# ChargeLevel.net
KiCad netlist of a schematic drawn in Altium Designer
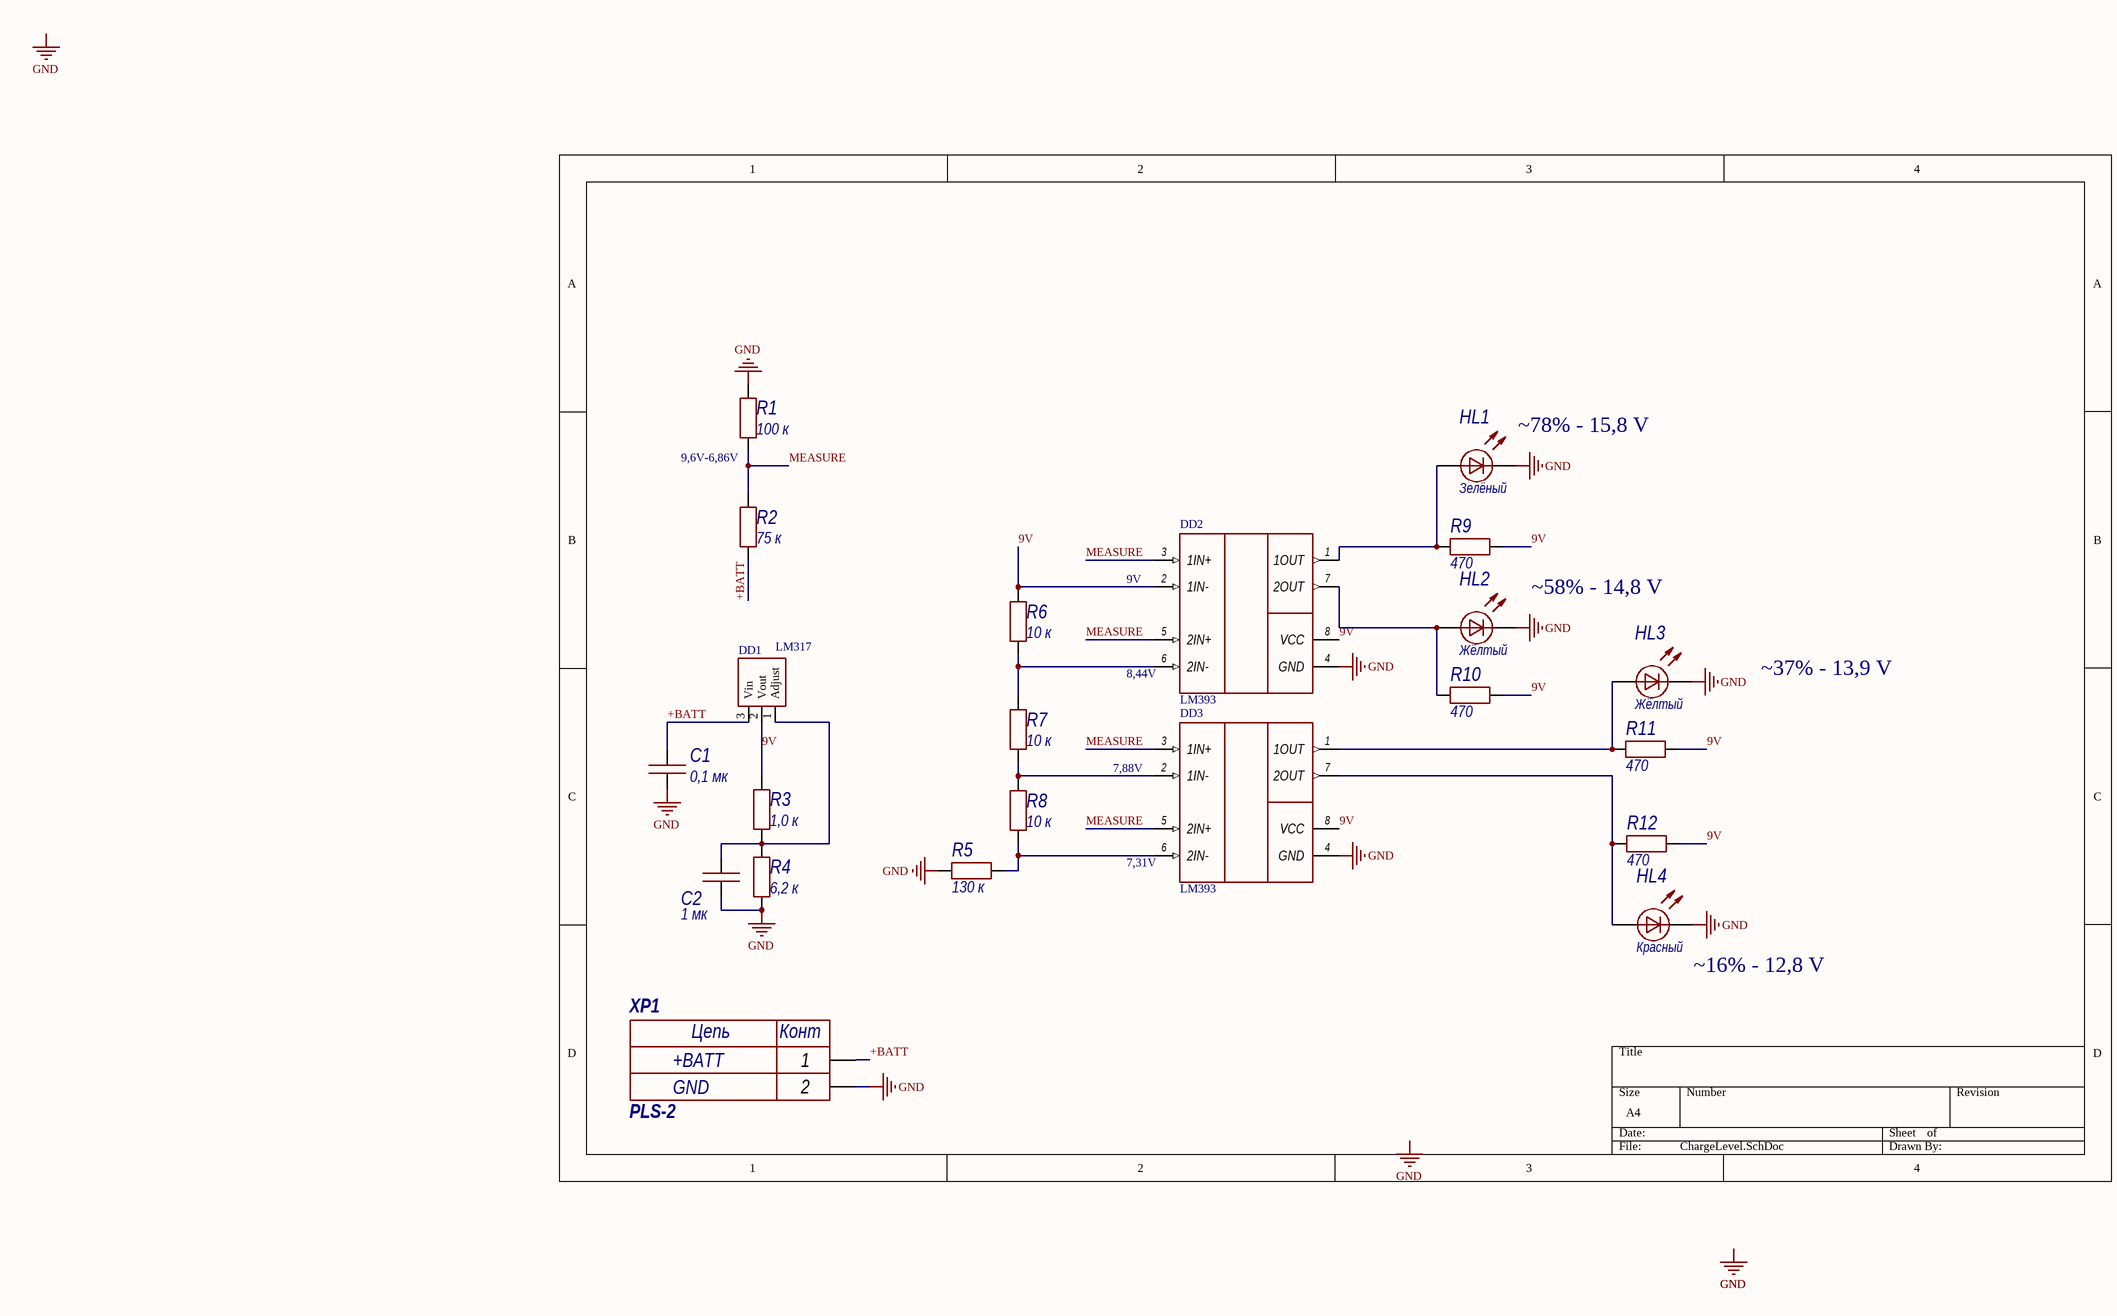
[diagram p0: ChargeLevel.SchDoc]

(export (version "E")
  (design (tool "Eeschema 10.0.6"))
  (components
    (comp (ref "C1")
      (value "0,1 мк")
      (footprint "0603C")
      (description "Конденсатор")
      (fields (field (name "PART NUMBER") "Capacitor"))
      (libsource (lib "Hydrolib") (part "Capacitor"))
    )
    (comp (ref "C2")
      (value "1 мк")
      (footprint "0603C")
      (description "Конденсатор")
      (fields (field (name "PART NUMBER") "Capacitor"))
      (libsource (lib "Hydrolib") (part "Capacitor"))
    )
    (comp (ref "DD1") (value "LM317") (footprint "TO-220") (libsource (lib "LM317") (part "LM317")))
    (comp (ref "DD2")
      (value "LM393")
      (footprint "SOIC-8")
      (description "Двойной маломощный компаратор напряжения")
      (fields
        (field (name "MF") "Texas Instruments")
        (field (name "MP") "LM393D")
        (field (name "АВТОР") "rreali")
      )
      (libsource (lib "Hydrolib") (part "LM393"))
    )
    (comp (ref "DD3")
      (value "LM393")
      (footprint "SOIC-8")
      (description "Двойной маломощный компаратор напряжения")
      (fields
        (field (name "MF") "Texas Instruments")
        (field (name "MP") "LM393D")
        (field (name "АВТОР") "rreali")
      )
      (libsource (lib "Hydrolib") (part "LM393"))
    )
    (comp (ref "HL1")
      (value "Зелёный")
      (footprint "0603D_green")
      (description "Светодиод 0603 Зелёный")
      (fields (field (name "PART NUMBER") "LED 0603 GREEN") (field (name "АВТОР") "rreali"))
      (libsource (lib "Hydrolib") (part "LED"))
    )
    (comp (ref "HL2")
      (value "Жёлтый")
      (footprint "0603D_yellow")
      (description "Светодиод 0603 Жёлтый")
      (fields (field (name "PART NUMBER") "LED 0603 YELLOW") (field (name "АВТОР") "rreali"))
      (libsource (lib "Hydrolib") (part "LED"))
    )
    (comp (ref "HL3")
      (value "Жёлтый")
      (footprint "0603D_yellow")
      (description "Светодиод 0603 Жёлтый")
      (fields (field (name "PART NUMBER") "LED 0603 YELLOW") (field (name "АВТОР") "rreali"))
      (libsource (lib "Hydrolib") (part "LED"))
    )
    (comp (ref "HL4")
      (value "Красный")
      (footprint "0603D_red")
      (description "Светодиод 0603 Красный")
      (fields (field (name "PART NUMBER") "LED 0603 RED") (field (name "АВТОР") "rreali"))
      (libsource (lib "Hydrolib") (part "LED"))
    )
    (comp (ref "R1")
      (value "100 к")
      (footprint "0603R")
      (description "Резистор номиналом 100 кОм 1%")
      (fields (field (name "PART NUMBER") "Resistor_100k_1_0603") (field (name "TOLERANCE") "1%"))
      (libsource (lib "Hydrolib") (part "Resistor"))
    )
    (comp (ref "R2")
      (value "75 к")
      (footprint "0603R")
      (description "Резистор номиналом 75 кОм 1%")
      (fields (field (name "PART NUMBER") "Resistor_75k_1_0603") (field (name "TOLERANCE") "1%"))
      (libsource (lib "Hydrolib") (part "Resistor"))
    )
    (comp (ref "R3")
      (value "1,0 к")
      (footprint "0603R")
      (description "Резистор номиналом 1,0 кОм 1%")
      (fields (field (name "PART NUMBER") "Resistor_1.0k_1_0603") (field (name "TOLERANCE") "1%"))
      (libsource (lib "Hydrolib") (part "Resistor"))
    )
    (comp (ref "R4")
      (value "6,2 к")
      (footprint "0603R")
      (description "Резистор номиналом 6,2 кОм 1%")
      (fields (field (name "PART NUMBER") "Resistor_6.2k_1_0603") (field (name "TOLERANCE") "1%"))
      (libsource (lib "Hydrolib") (part "Resistor"))
    )
    (comp (ref "R5")
      (value "130 к")
      (footprint "0603R")
      (description "Резистор номиналом 130 кОм 1%")
      (fields (field (name "PART NUMBER") "Resistor_130k_1_0603") (field (name "TOLERANCE") "1%"))
      (libsource (lib "") (part "Resistor_1"))
    )
    (comp (ref "R6")
      (value "10 к")
      (footprint "0603R")
      (description "Резистор номиналом 10 кОм 1%")
      (fields (field (name "PART NUMBER") "Resistor_10k_1_0603") (field (name "TOLERANCE") "1%"))
      (libsource (lib "Hydrolib") (part "Resistor"))
    )
    (comp (ref "R7")
      (value "10 к")
      (footprint "0603R")
      (description "Резистор номиналом 10 кОм 1%")
      (fields (field (name "PART NUMBER") "Resistor_10k_1_0603") (field (name "TOLERANCE") "1%"))
      (libsource (lib "Hydrolib") (part "Resistor"))
    )
    (comp (ref "R8")
      (value "10 к")
      (footprint "0603R")
      (description "Резистор номиналом 10 кОм 1%")
      (fields (field (name "PART NUMBER") "Resistor_10k_1_0603") (field (name "TOLERANCE") "1%"))
      (libsource (lib "Hydrolib") (part "Resistor"))
    )
    (comp (ref "R9")
      (value "470")
      (footprint "0603R")
      (description "Резистор номиналом 470 Ом 1%")
      (fields (field (name "PART NUMBER") "Resistor_470_1_0603") (field (name "TOLERANCE") "1%"))
      (libsource (lib "") (part "Resistor_1"))
    )
    (comp (ref "R10")
      (value "470")
      (footprint "0603R")
      (description "Резистор номиналом 470 Ом 1%")
      (fields (field (name "PART NUMBER") "Resistor_470_1_0603") (field (name "TOLERANCE") "1%"))
      (libsource (lib "") (part "Resistor_1"))
    )
    (comp (ref "R11")
      (value "470")
      (footprint "0603R")
      (description "Резистор номиналом 470 Ом 1%")
      (fields (field (name "PART NUMBER") "Resistor_470_1_0603") (field (name "TOLERANCE") "1%"))
      (libsource (lib "") (part "Resistor_1"))
    )
    (comp (ref "R12")
      (value "470")
      (footprint "0603R")
      (description "Резистор номиналом 470 Ом 1%")
      (fields (field (name "PART NUMBER") "Resistor_470_1_0603") (field (name "TOLERANCE") "1%"))
      (libsource (lib "") (part "Resistor_1"))
    )
    (comp (ref "XP1")
      (value "PLS-2")
      (footprint "PLS2")
      (description "Гребенка 2 пина")
      (fields (field (name "VALUE2") "GND") (field (name "VALUE1") "+BATT") (field (name "АВТОР") "rreali"))
      (libsource (lib "Hydrolib") (part "Conn_2pin"))
    )
  )
  (nets
    (net (code "1") (name "/+BATT") (class "Default")
      (node (ref "C1") (pin "1") (pinfunction "1_1") (pintype "passive"))
      (node (ref "DD1") (pin "3") (pinfunction "Vin_3") (pintype "passive"))
      (node (ref "R2") (pin "1") (pinfunction "1_1") (pintype "passive"))
      (node (ref "XP1") (pin "1") (pinfunction "1_1") (pintype "passive"))
    )
    (net (code "2") (name "/9V") (class "Default")
      (node (ref "DD1") (pin "2") (pinfunction "Vout_2") (pintype "passive"))
      (node (ref "DD2") (pin "2") (pinfunction "1IN-_2") (pintype "input"))
      (node (ref "DD2") (pin "8") (pinfunction "VCC_8") (pintype "power_in"))
      (node (ref "DD3") (pin "8") (pinfunction "VCC_8") (pintype "power_in"))
      (node (ref "R10") (pin "2") (pinfunction "2_2") (pintype "passive"))
      (node (ref "R11") (pin "2") (pinfunction "2_2") (pintype "passive"))
      (node (ref "R12") (pin "2") (pinfunction "2_2") (pintype "passive"))
      (node (ref "R3") (pin "2") (pinfunction "2_2") (pintype "passive"))
      (node (ref "R6") (pin "2") (pinfunction "2_2") (pintype "passive"))
      (node (ref "R9") (pin "2") (pinfunction "2_2") (pintype "passive"))
    )
    (net (code "3") (name "/MEASURE") (class "Default")
      (node (ref "DD2") (pin "3") (pinfunction "1IN+_3") (pintype "input"))
      (node (ref "DD2") (pin "5") (pinfunction "2IN+_5") (pintype "input"))
      (node (ref "DD3") (pin "3") (pinfunction "1IN+_3") (pintype "input"))
      (node (ref "DD3") (pin "5") (pinfunction "2IN+_5") (pintype "input"))
      (node (ref "R1") (pin "1") (pinfunction "1_1") (pintype "passive"))
      (node (ref "R2") (pin "2") (pinfunction "2_2") (pintype "passive"))
    )
    (net (code "4") (name "GND") (class "Default")
      (node (ref "C1") (pin "2") (pinfunction "2_2") (pintype "passive"))
      (node (ref "C2") (pin "2") (pinfunction "2_2") (pintype "passive"))
      (node (ref "DD2") (pin "4") (pinfunction "GND_4") (pintype "power_in"))
      (node (ref "DD3") (pin "4") (pinfunction "GND_4") (pintype "power_in"))
      (node (ref "HL1") (pin "2") (pinfunction "2_2") (pintype "passive"))
      (node (ref "HL2") (pin "2") (pinfunction "2_2") (pintype "passive"))
      (node (ref "HL3") (pin "2") (pinfunction "2_2") (pintype "passive"))
      (node (ref "HL4") (pin "2") (pinfunction "2_2") (pintype "passive"))
      (node (ref "R1") (pin "2") (pinfunction "2_2") (pintype "passive"))
      (node (ref "R4") (pin "1") (pinfunction "1_1") (pintype "passive"))
      (node (ref "R5") (pin "1") (pinfunction "1_1") (pintype "passive"))
      (node (ref "XP1") (pin "2") (pinfunction "2_2") (pintype "passive"))
    )
    (net (code "5") (name "Net-(DD1-Adjust)") (class "Default")
      (node (ref "C2") (pin "1") (pinfunction "1_1") (pintype "passive"))
      (node (ref "DD1") (pin "1") (pinfunction "Adjust_1") (pintype "passive"))
      (node (ref "R3") (pin "1") (pinfunction "1_1") (pintype "passive"))
      (node (ref "R4") (pin "2") (pinfunction "2_2") (pintype "passive"))
    )
    (net (code "6") (name "Net-(DD2-1OUT)") (class "Default")
      (node (ref "DD2") (pin "1") (pinfunction "1OUT_1") (pintype "output"))
      (node (ref "HL1") (pin "1") (pinfunction "1_1") (pintype "passive"))
      (node (ref "R9") (pin "1") (pinfunction "1_1") (pintype "passive"))
    )
    (net (code "7") (name "Net-(DD2-2IN-)") (class "Default")
      (node (ref "DD2") (pin "6") (pinfunction "2IN-_6") (pintype "input"))
      (node (ref "R6") (pin "1") (pinfunction "1_1") (pintype "passive"))
      (node (ref "R7") (pin "2") (pinfunction "2_2") (pintype "passive"))
    )
    (net (code "8") (name "Net-(DD2-2OUT)") (class "Default")
      (node (ref "DD2") (pin "7") (pinfunction "2OUT_7") (pintype "output"))
      (node (ref "HL2") (pin "1") (pinfunction "1_1") (pintype "passive"))
      (node (ref "R10") (pin "1") (pinfunction "1_1") (pintype "passive"))
    )
    (net (code "9") (name "Net-(DD3-1IN-)") (class "Default")
      (node (ref "DD3") (pin "2") (pinfunction "1IN-_2") (pintype "input"))
      (node (ref "R7") (pin "1") (pinfunction "1_1") (pintype "passive"))
      (node (ref "R8") (pin "2") (pinfunction "2_2") (pintype "passive"))
    )
    (net (code "10") (name "Net-(DD3-1OUT)") (class "Default")
      (node (ref "DD3") (pin "1") (pinfunction "1OUT_1") (pintype "output"))
      (node (ref "HL3") (pin "1") (pinfunction "1_1") (pintype "passive"))
      (node (ref "R11") (pin "1") (pinfunction "1_1") (pintype "passive"))
    )
    (net (code "11") (name "Net-(DD3-2IN-)") (class "Default")
      (node (ref "DD3") (pin "6") (pinfunction "2IN-_6") (pintype "input"))
      (node (ref "R5") (pin "2") (pinfunction "2_2") (pintype "passive"))
      (node (ref "R8") (pin "1") (pinfunction "1_1") (pintype "passive"))
    )
    (net (code "12") (name "Net-(DD3-2OUT)") (class "Default")
      (node (ref "DD3") (pin "7") (pinfunction "2OUT_7") (pintype "output"))
      (node (ref "HL4") (pin "1") (pinfunction "1_1") (pintype "passive"))
      (node (ref "R12") (pin "1") (pinfunction "1_1") (pintype "passive"))
    )
  )
)
